# 08_-_CPU_USB.net
KiCad netlist of a schematic drawn in Altium Designer
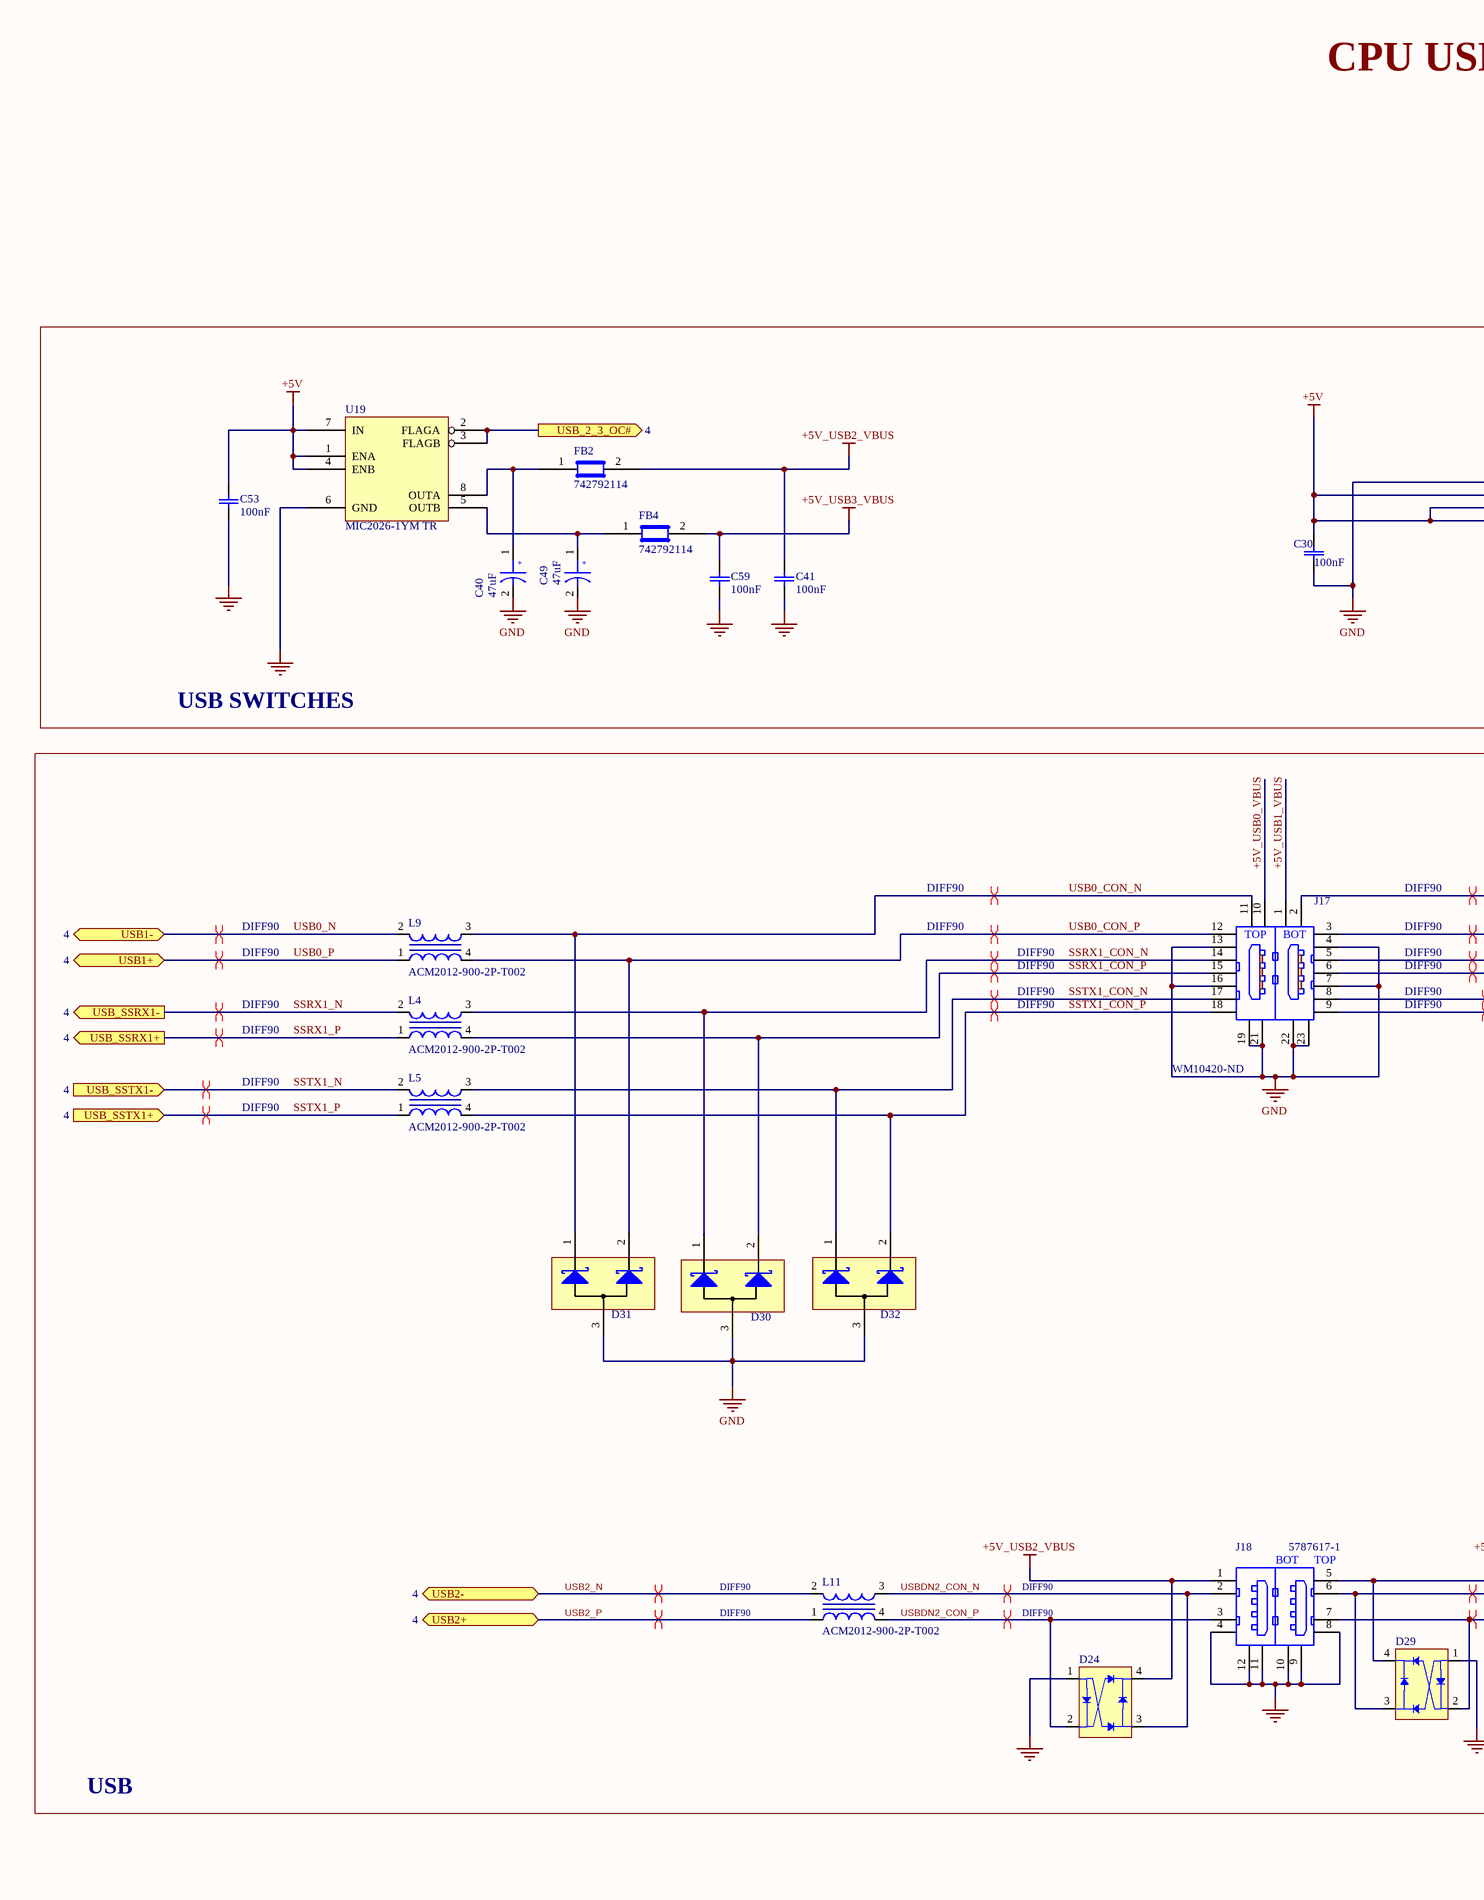
[diagram p0: [08] - CPU USB.SchDoc, left]
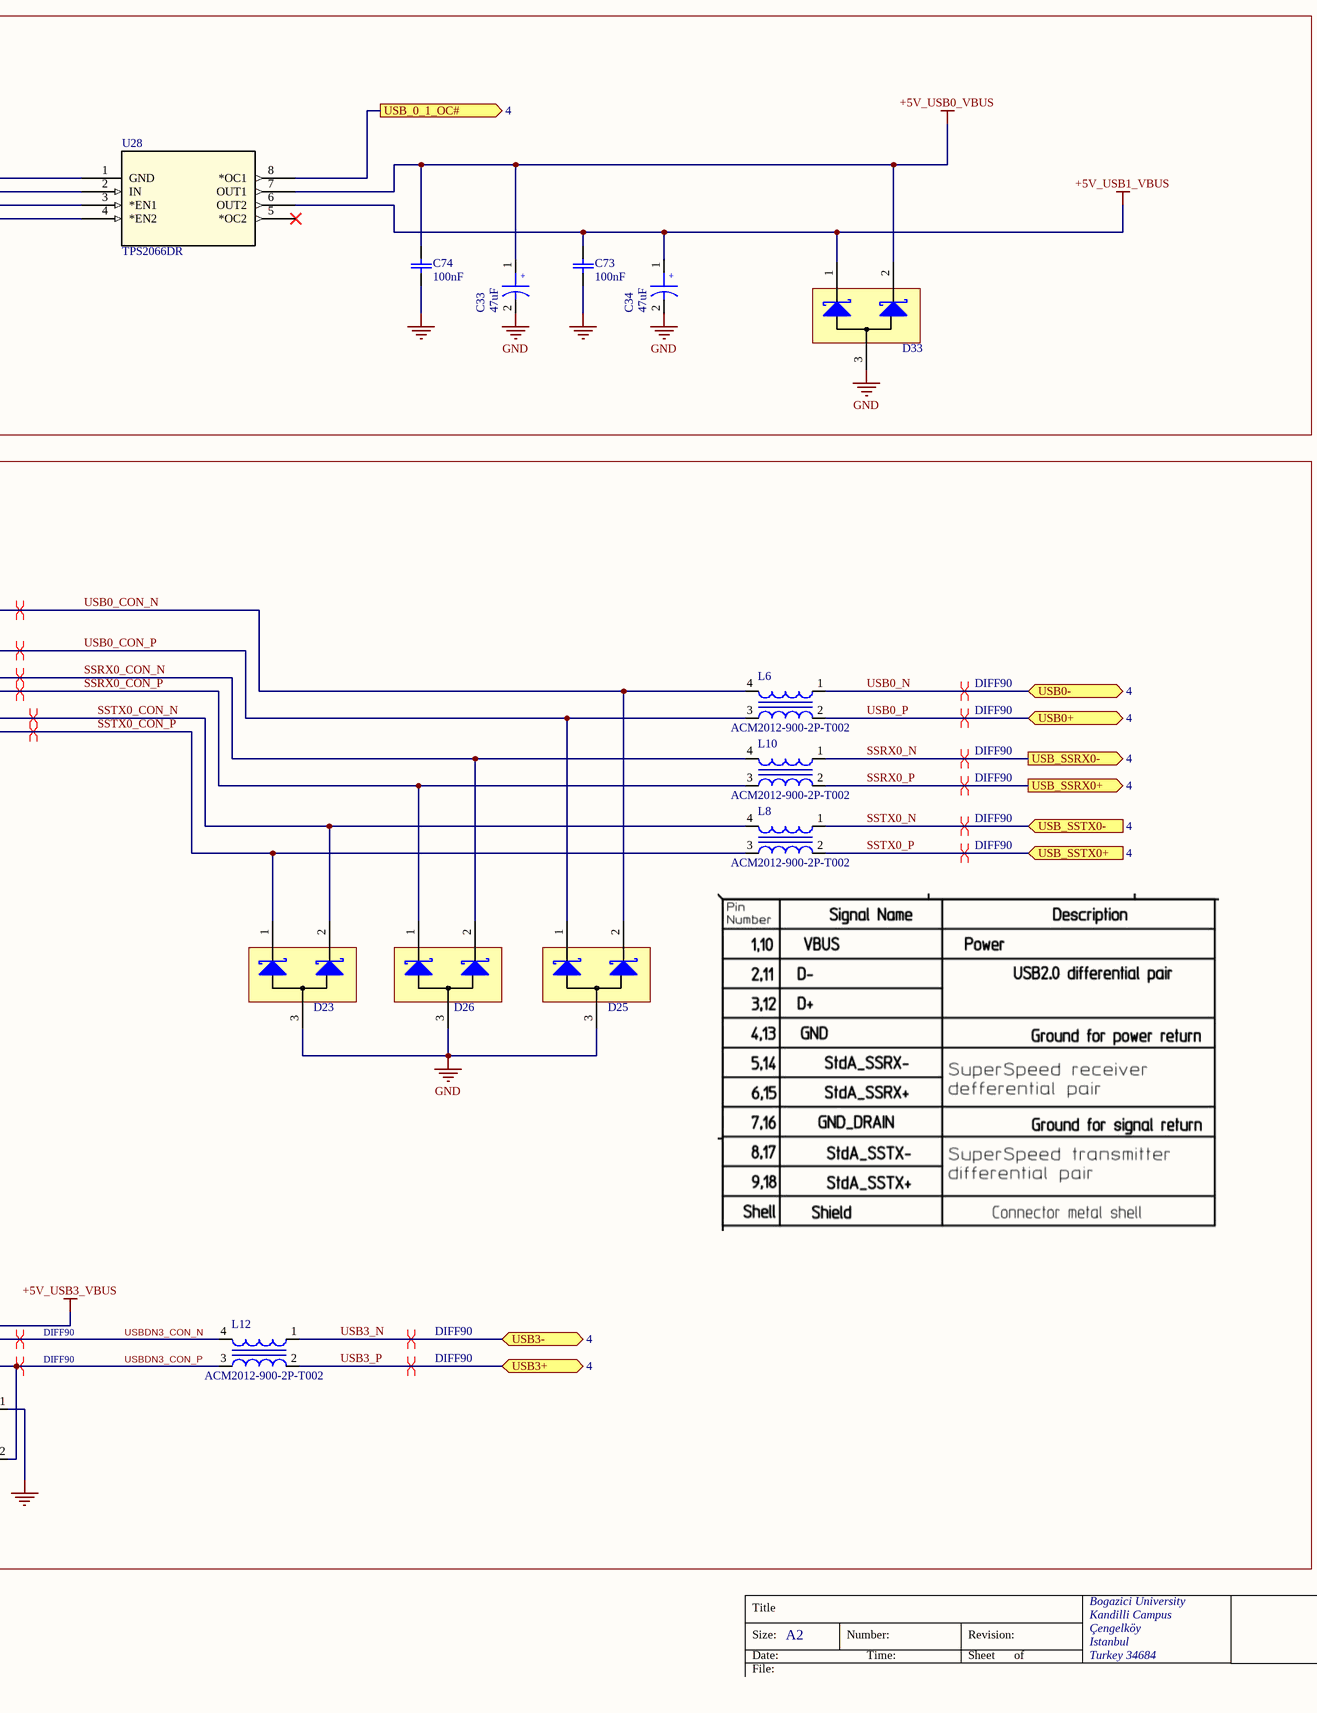
[diagram p1: [08] - CPU USB.SchDoc, right]

(export (version "E")
  (design (tool "Eeschema 10.0.6"))
  (components
    (comp (ref "C30")
      (value "100nF")
      (footprint "C0402")
      (description "CAP CER 0.1UF 50V X8R 0603")
      (fields (field (name "TOLERANCE") "±10%"))
      (libsource (lib "SYNCBOX_V3I1") (part "CL05A104KA5NNNC"))
    )
    (comp (ref "C33")
      (value "47uF")
      (footprint "CAP_P-B")
      (description "CAP ALUM POLY 47UF 20% 16V SMD")
      (fields
        (field (name "TOLERANCE") "±20%")
        (field (name ".CHECKED PCB") "CHK")
        (field (name ".CHECKED SCH") "CHK")
      )
      (libsource (lib "SYNCBOX_V3I1") (part "PCG1C470MCL1GS"))
    )
    (comp (ref "C34")
      (value "47uF")
      (footprint "CAP_P-B")
      (description "CAP ALUM POLY 47UF 20% 16V SMD")
      (fields
        (field (name "TOLERANCE") "±20%")
        (field (name ".CHECKED PCB") "CHK")
        (field (name ".CHECKED SCH") "CHK")
      )
      (libsource (lib "SYNCBOX_V3I1") (part "PCG1C470MCL1GS"))
    )
    (comp (ref "C40")
      (value "47uF")
      (footprint "CAP_P-B")
      (description "CAP ALUM POLY 47UF 20% 16V SMD")
      (fields
        (field (name "TOLERANCE") "±20%")
        (field (name ".CHECKED PCB") "CHK")
        (field (name ".CHECKED SCH") "CHK")
      )
      (libsource (lib "SYNCBOX_V3I1") (part "PCG1C470MCL1GS"))
    )
    (comp (ref "C41")
      (value "100nF")
      (footprint "C0402")
      (description "CAP CER 0.1UF 50V X8R 0603")
      (fields (field (name "TOLERANCE") "±10%"))
      (libsource (lib "SYNCBOX_V3I1") (part "CL05A104KA5NNNC"))
    )
    (comp (ref "C49")
      (value "47uF")
      (footprint "CAP_P-B")
      (description "CAP ALUM POLY 47UF 20% 16V SMD")
      (fields
        (field (name "TOLERANCE") "±20%")
        (field (name ".CHECKED PCB") "CHK")
        (field (name ".CHECKED SCH") "CHK")
      )
      (libsource (lib "SYNCBOX_V3I1") (part "PCG1C470MCL1GS"))
    )
    (comp (ref "C53")
      (value "100nF")
      (footprint "C0402")
      (description "CAP CER 0.1UF 50V X8R 0603")
      (fields (field (name "TOLERANCE") "±10%"))
      (libsource (lib "SYNCBOX_V3I1") (part "CL05A104KA5NNNC"))
    )
    (comp (ref "C59")
      (value "100nF")
      (footprint "C0402")
      (description "CAP CER 0.1UF 50V X8R 0603")
      (fields (field (name "TOLERANCE") "±10%"))
      (libsource (lib "SYNCBOX_V3I1") (part "CL05A104KA5NNNC"))
    )
    (comp (ref "C73")
      (value "100nF")
      (footprint "C0402")
      (description "CAP CER 0.1UF 50V X8R 0603")
      (fields (field (name "TOLERANCE") "±10%"))
      (libsource (lib "SYNCBOX_V3I1") (part "CL05A104KA5NNNC"))
    )
    (comp (ref "C74")
      (value "100nF")
      (footprint "C0402")
      (description "CAP CER 0.1UF 50V X8R 0603")
      (fields (field (name "TOLERANCE") "±10%"))
      (libsource (lib "SYNCBOX_V3I1") (part "CL05A104KA5NNNC"))
    )
    (comp (ref "D23")
      (value "ESD5V3U2U03FH6327XTSA1")
      (footprint "PG-TSLP-3-7")
      (description "TVS DIODE 5.3V 15V TSFP-3")
      (fields
        (field (name "BASE PART NUMBER") "ESD5V3")
        (field (name ".CHECKED PCB") "CHK")
        (field (name ".CHECKED SCH") "CHK")
      )
      (libsource (lib "SYNCBOX_V3I1") (part "ESD5V3U2U03FH6327XTSA1"))
    )
    (comp (ref "D24")
      (value "BAS4002ARPPE6327HTSA1")
      (footprint "SOT143B")
      (description "DIODE BRIDGE 40V 200MA SOT 143")
      (fields (field (name "BASE PART NUMBER") "BAS4002"))
      (libsource (lib "") (part "BAS4002ARPPE6327HTSA1_1"))
    )
    (comp (ref "D25")
      (value "ESD5V3U2U03FH6327XTSA1")
      (footprint "PG-TSLP-3-7")
      (description "TVS DIODE 5.3V 15V TSFP-3")
      (fields
        (field (name "BASE PART NUMBER") "ESD5V3")
        (field (name ".CHECKED PCB") "CHK")
        (field (name ".CHECKED SCH") "CHK")
      )
      (libsource (lib "SYNCBOX_V3I1") (part "ESD5V3U2U03FH6327XTSA1"))
    )
    (comp (ref "D26")
      (value "ESD5V3U2U03FH6327XTSA1")
      (footprint "PG-TSLP-3-7")
      (description "TVS DIODE 5.3V 15V TSFP-3")
      (fields
        (field (name "BASE PART NUMBER") "ESD5V3")
        (field (name ".CHECKED PCB") "CHK")
        (field (name ".CHECKED SCH") "CHK")
      )
      (libsource (lib "SYNCBOX_V3I1") (part "ESD5V3U2U03FH6327XTSA1"))
    )
    (comp (ref "D29")
      (value "BAS4002ARPPE6327HTSA1")
      (footprint "SOT143B")
      (description "DIODE BRIDGE 40V 200MA SOT 143")
      (fields (field (name "BASE PART NUMBER") "BAS4002"))
      (libsource (lib "SYNCBOX_V3I1") (part "BAS4002ARPPE6327HTSA1"))
    )
    (comp (ref "D30")
      (value "ESD5V3U2U03FH6327XTSA1")
      (footprint "PG-TSLP-3-7")
      (description "TVS DIODE 5.3V 15V TSFP-3")
      (fields
        (field (name "BASE PART NUMBER") "ESD5V3")
        (field (name ".CHECKED PCB") "CHK")
        (field (name ".CHECKED SCH") "CHK")
      )
      (libsource (lib "SYNCBOX_V3I1") (part "ESD5V3U2U03FH6327XTSA1"))
    )
    (comp (ref "D31")
      (value "ESD5V3U2U03FH6327XTSA1")
      (footprint "PG-TSLP-3-7")
      (description "TVS DIODE 5.3V 15V TSFP-3")
      (fields
        (field (name "BASE PART NUMBER") "ESD5V3")
        (field (name ".CHECKED PCB") "CHK")
        (field (name ".CHECKED SCH") "CHK")
      )
      (libsource (lib "SYNCBOX_V3I1") (part "ESD5V3U2U03FH6327XTSA1"))
    )
    (comp (ref "D32")
      (value "ESD5V3U2U03FH6327XTSA1")
      (footprint "PG-TSLP-3-7")
      (description "TVS DIODE 5.3V 15V TSFP-3")
      (fields
        (field (name "BASE PART NUMBER") "ESD5V3")
        (field (name ".CHECKED PCB") "CHK")
        (field (name ".CHECKED SCH") "CHK")
      )
      (libsource (lib "SYNCBOX_V3I1") (part "ESD5V3U2U03FH6327XTSA1"))
    )
    (comp (ref "D33")
      (value "ESD5V3U2U03FH6327XTSA1")
      (footprint "PG-TSLP-3-7")
      (description "TVS DIODE 5.3V 15V TSFP-3")
      (fields
        (field (name "BASE PART NUMBER") "ESD5V3")
        (field (name ".CHECKED PCB") "CHK")
        (field (name ".CHECKED SCH") "CHK")
      )
      (libsource (lib "SYNCBOX_V3I1") (part "ESD5V3U2U03FH6327XTSA1"))
    )
    (comp (ref "FB2")
      (value "742792114")
      (footprint "Ferrite bead")
      (description "FERRITE BEAD 50 OHM 1206 1LN")
      (fields (field (name ".CHECKED PCB") "CHK") (field (name ".CHECKED SCH") "CHK"))
      (libsource (lib "SYNCBOX_V3I1") (part "FB742792114"))
    )
    (comp (ref "FB4")
      (value "742792114")
      (footprint "Ferrite bead")
      (description "FERRITE BEAD 50 OHM 1206 1LN")
      (fields (field (name ".CHECKED PCB") "CHK") (field (name ".CHECKED SCH") "CHK"))
      (libsource (lib "SYNCBOX_V3I1") (part "FB742792114"))
    )
    (comp (ref "J17")
      (value "WM10420-ND")
      (footprint "USB 3 STACK")
      (description "USB 3.0 RA DUAL REC TH TYPE A")
      (fields (field (name ".CHECKED PCB") "CHK") (field (name ".CHECKED SCH") "CHK"))
      (libsource (lib "SYNCBOX_V3I1") (part "USB 3"))
    )
    (comp (ref "J18")
      (value "5787617-1")
      (footprint "USB-2A")
      (description "CONN RCPT R/A 4OVER4POS GOLD PCB")
      (fields
        (field (name "MANUFACTURER") "TE Connectivity")
        (field (name ".CHECKED PCB") "CHK")
        (field (name ".CHECKED SCH") "CHK")
      )
      (libsource (lib "SYNCBOX_V3I1") (part "5787617-1"))
    )
    (comp (ref "L4")
      (value "ACM2012-900-2P-T002")
      (footprint "iMX6 Rex Development Baseboard V1I1_PCB:ACM2012")
      (description "CHOKE COMM MODE 90 OHM .4A SMD")
      (fields
        (field (name "MANUFACTURER") "TDK Corporation")
        (field (name "TOLERANCE") "±1%")
        (field (name ".CHECKED PCB") "CHK")
        (field (name ".CHECKED SCH") "CHK")
      )
      (libsource (lib "SYNCBOX_V3I1") (part "ACM2012-900-2P-T002"))
    )
    (comp (ref "L5")
      (value "ACM2012-900-2P-T002")
      (footprint "iMX6 Rex Development Baseboard V1I1_PCB:ACM2012")
      (description "CHOKE COMM MODE 90 OHM .4A SMD")
      (fields
        (field (name "MANUFACTURER") "TDK Corporation")
        (field (name "TOLERANCE") "±1%")
        (field (name ".CHECKED PCB") "CHK")
        (field (name ".CHECKED SCH") "CHK")
      )
      (libsource (lib "SYNCBOX_V3I1") (part "ACM2012-900-2P-T002"))
    )
    (comp (ref "L6")
      (value "ACM2012-900-2P-T002")
      (footprint "iMX6 Rex Development Baseboard V1I1_PCB:ACM2012")
      (description "CHOKE COMM MODE 90 OHM .4A SMD")
      (fields
        (field (name "MANUFACTURER") "TDK Corporation")
        (field (name "TOLERANCE") "±1%")
        (field (name ".CHECKED PCB") "CHK")
        (field (name ".CHECKED SCH") "CHK")
      )
      (libsource (lib "SYNCBOX_V3I1") (part "ACM2012-900-2P-T002"))
    )
    (comp (ref "L8")
      (value "ACM2012-900-2P-T002")
      (footprint "iMX6 Rex Development Baseboard V1I1_PCB:ACM2012")
      (description "CHOKE COMM MODE 90 OHM .4A SMD")
      (fields
        (field (name "MANUFACTURER") "TDK Corporation")
        (field (name "TOLERANCE") "±1%")
        (field (name ".CHECKED PCB") "CHK")
        (field (name ".CHECKED SCH") "CHK")
      )
      (libsource (lib "SYNCBOX_V3I1") (part "ACM2012-900-2P-T002"))
    )
    (comp (ref "L9")
      (value "ACM2012-900-2P-T002")
      (footprint "iMX6 Rex Development Baseboard V1I1_PCB:ACM2012")
      (description "CHOKE COMM MODE 90 OHM .4A SMD")
      (fields
        (field (name "MANUFACTURER") "TDK Corporation")
        (field (name "TOLERANCE") "±1%")
        (field (name ".CHECKED PCB") "CHK")
        (field (name ".CHECKED SCH") "CHK")
      )
      (libsource (lib "SYNCBOX_V3I1") (part "ACM2012-900-2P-T002"))
    )
    (comp (ref "L10")
      (value "ACM2012-900-2P-T002")
      (footprint "iMX6 Rex Development Baseboard V1I1_PCB:ACM2012")
      (description "CHOKE COMM MODE 90 OHM .4A SMD")
      (fields
        (field (name "MANUFACTURER") "TDK Corporation")
        (field (name "TOLERANCE") "±1%")
        (field (name ".CHECKED PCB") "CHK")
        (field (name ".CHECKED SCH") "CHK")
      )
      (libsource (lib "SYNCBOX_V3I1") (part "ACM2012-900-2P-T002"))
    )
    (comp (ref "L11")
      (value "ACM2012-900-2P-T002")
      (footprint "iMX6 Rex Development Baseboard V1I1_PCB:ACM2012")
      (description "CHOKE COMM MODE 90 OHM .4A SMD")
      (fields
        (field (name "MANUFACTURER") "TDK Corporation")
        (field (name "TOLERANCE") "±1%")
        (field (name ".CHECKED PCB") "CHK")
        (field (name ".CHECKED SCH") "CHK")
      )
      (libsource (lib "SYNCBOX_V3I1") (part "ACM2012-900-2P-T002"))
    )
    (comp (ref "L12")
      (value "ACM2012-900-2P-T002")
      (footprint "iMX6 Rex Development Baseboard V1I1_PCB:ACM2012")
      (description "CHOKE COMM MODE 90 OHM .4A SMD")
      (fields
        (field (name "MANUFACTURER") "TDK Corporation")
        (field (name "TOLERANCE") "±1%")
        (field (name ".CHECKED PCB") "CHK")
        (field (name ".CHECKED SCH") "CHK")
      )
      (libsource (lib "SYNCBOX_V3I1") (part "ACM2012-900-2P-T002"))
    )
    (comp (ref "U19")
      (value "MIC2026-1YM TR")
      (footprint "8_SOIC_3.9MM")
      (description "IC SW DISTRIBUTION 2CHAN 8SOIC")
      (fields
        (field (name "MANUFACTURER") "Micrel Inc")
        (field (name ".CHECKED PCB") "CHK")
        (field (name ".CHECKED SCH") "CHK")
      )
      (libsource (lib "SYNCBOX_V3I1") (part "MIC2026-1YM TR"))
    )
    (comp (ref "U28")
      (value "TPS2066DR")
      (footprint "D8")
      (description "IC PWR DIST SW DUAL 8SOIC")
      (fields (field (name "MANUFACTURER") "Texas Instruments") (field (name "BASE PART NUMBER") "TPS2066"))
      (libsource (lib "SYNCBOX_V3I1") (part "TPS2066DR"))
    )
  )
  (nets
    (net (code "1") (name "+5V") (class "Default")
      (node (ref "C30") (pin "2") (pinfunction "2_2") (pintype "passive"))
      (node (ref "C53") (pin "2") (pinfunction "2_2") (pintype "passive"))
      (node (ref "U19") (pin "1") (pinfunction "ENA_1") (pintype "passive"))
      (node (ref "U19") (pin "4") (pinfunction "ENB_4") (pintype "passive"))
      (node (ref "U19") (pin "7") (pinfunction "IN_7") (pintype "power_in"))
      (node (ref "U28") (pin "2") (pinfunction "IN_2") (pintype "input"))
      (node (ref "U28") (pin "3") (pinfunction "*EN1_3") (pintype "input"))
      (node (ref "U28") (pin "4") (pinfunction "*EN2_4") (pintype "input"))
    )
    (net (code "2") (name "+5V_USB0_VBUS") (class "Default")
      (node (ref "C33") (pin "1") (pinfunction "1_1") (pintype "passive"))
      (node (ref "C74") (pin "2") (pinfunction "2_2") (pintype "passive"))
      (node (ref "D33") (pin "2") (pinfunction "2_2") (pintype "passive"))
      (node (ref "J17") (pin "10") (pinfunction "VBUS2_10") (pintype "power_in"))
      (node (ref "U28") (pin "7") (pinfunction "OUT1_7") (pintype "output"))
    )
    (net (code "3") (name "+5V_USB1_VBUS") (class "Default")
      (node (ref "C34") (pin "1") (pinfunction "1_1") (pintype "passive"))
      (node (ref "C73") (pin "2") (pinfunction "2_2") (pintype "passive"))
      (node (ref "D33") (pin "1") (pinfunction "1_1") (pintype "passive"))
      (node (ref "J17") (pin "1") (pinfunction "VBUS1_1") (pintype "power_in"))
      (node (ref "U28") (pin "6") (pinfunction "OUT2_6") (pintype "output"))
    )
    (net (code "4") (name "+5V_USB2_VBUS") (class "Default")
      (node (ref "C41") (pin "2") (pinfunction "2_2") (pintype "passive"))
      (node (ref "D24") (pin "4") (pinfunction "4_4") (pintype "passive"))
      (node (ref "FB2") (pin "2") (pinfunction "2_2") (pintype "passive"))
      (node (ref "J18") (pin "1") (pinfunction "VBUS_1") (pintype "passive"))
    )
    (net (code "5") (name "+5V_USB3_VBUS") (class "Default")
      (node (ref "C59") (pin "2") (pinfunction "2_2") (pintype "passive"))
      (node (ref "D29") (pin "4") (pinfunction "4_4") (pintype "passive"))
      (node (ref "FB4") (pin "2") (pinfunction "2_2") (pintype "passive"))
      (node (ref "J18") (pin "5") (pinfunction "VBUS2_5") (pintype "passive"))
    )
    (net (code "6") (name "/SSRX0_CON_N") (class "Default")
      (node (ref "D26") (pin "2") (pinfunction "2_2") (pintype "passive"))
      (node (ref "J17") (pin "5") (pinfunction "SSRX0-_5") (pintype "passive"))
      (node (ref "L10") (pin "4") (pinfunction "4_4") (pintype "passive"))
    )
    (net (code "7") (name "/SSRX0_CON_P") (class "Default")
      (node (ref "D26") (pin "1") (pinfunction "1_1") (pintype "passive"))
      (node (ref "J17") (pin "6") (pinfunction "SSRX0+_6") (pintype "passive"))
      (node (ref "L10") (pin "3") (pinfunction "3_3") (pintype "passive"))
    )
    (net (code "8") (name "/SSRX0_N") (class "Default")
      (node (ref "L10") (pin "1") (pinfunction "1_1") (pintype "passive"))
    )
    (net (code "9") (name "/SSRX0_P") (class "Default")
      (node (ref "L10") (pin "2") (pinfunction "2_2") (pintype "passive"))
    )
    (net (code "10") (name "/SSRX1_CON_N") (class "Default")
      (node (ref "D30") (pin "1") (pinfunction "1_1") (pintype "passive"))
      (node (ref "J17") (pin "14") (pinfunction "SSRX2-_14") (pintype "passive"))
      (node (ref "L4") (pin "3") (pinfunction "3_3") (pintype "passive"))
    )
    (net (code "11") (name "/SSRX1_CON_P") (class "Default")
      (node (ref "D30") (pin "2") (pinfunction "2_2") (pintype "passive"))
      (node (ref "J17") (pin "15") (pinfunction "SSRX2+_15") (pintype "passive"))
      (node (ref "L4") (pin "4") (pinfunction "4_4") (pintype "passive"))
    )
    (net (code "12") (name "/SSRX1_N") (class "Default")
      (node (ref "L4") (pin "2") (pinfunction "2_2") (pintype "passive"))
    )
    (net (code "13") (name "/SSRX1_P") (class "Default")
      (node (ref "L4") (pin "1") (pinfunction "1_1") (pintype "passive"))
    )
    (net (code "14") (name "/SSTX0_CON_N") (class "Default")
      (node (ref "D23") (pin "2") (pinfunction "2_2") (pintype "passive"))
      (node (ref "J17") (pin "8") (pinfunction "SSTX0-_8") (pintype "passive"))
      (node (ref "L8") (pin "4") (pinfunction "4_4") (pintype "passive"))
    )
    (net (code "15") (name "/SSTX0_CON_P") (class "Default")
      (node (ref "D23") (pin "1") (pinfunction "1_1") (pintype "passive"))
      (node (ref "J17") (pin "9") (pinfunction "SSTX0+_9") (pintype "passive"))
      (node (ref "L8") (pin "3") (pinfunction "3_3") (pintype "passive"))
    )
    (net (code "16") (name "/SSTX0_N") (class "Default")
      (node (ref "L8") (pin "1") (pinfunction "1_1") (pintype "passive"))
    )
    (net (code "17") (name "/SSTX0_P") (class "Default")
      (node (ref "L8") (pin "2") (pinfunction "2_2") (pintype "passive"))
    )
    (net (code "18") (name "/SSTX1_CON_N") (class "Default")
      (node (ref "D32") (pin "1") (pinfunction "1_1") (pintype "passive"))
      (node (ref "J17") (pin "17") (pinfunction "SSTX2-_17") (pintype "passive"))
      (node (ref "L5") (pin "3") (pinfunction "3_3") (pintype "passive"))
    )
    (net (code "19") (name "/SSTX1_CON_P") (class "Default")
      (node (ref "D32") (pin "2") (pinfunction "2_2") (pintype "passive"))
      (node (ref "J17") (pin "18") (pinfunction "SSTX2+_18") (pintype "passive"))
      (node (ref "L5") (pin "4") (pinfunction "4_4") (pintype "passive"))
    )
    (net (code "20") (name "/SSTX1_N") (class "Default")
      (node (ref "L5") (pin "2") (pinfunction "2_2") (pintype "passive"))
    )
    (net (code "21") (name "/SSTX1_P") (class "Default")
      (node (ref "L5") (pin "1") (pinfunction "1_1") (pintype "passive"))
    )
    (net (code "22") (name "/USB0_CON_N") (class "Default")
      (node (ref "D25") (pin "2") (pinfunction "2_2") (pintype "passive"))
      (node (ref "D31") (pin "1") (pinfunction "1_1") (pintype "passive"))
      (node (ref "J17") (pin "11") (pinfunction "D2-_11") (pintype "passive"))
      (node (ref "J17") (pin "2") (pinfunction "D1-_2") (pintype "passive"))
      (node (ref "L6") (pin "4") (pinfunction "4_4") (pintype "passive"))
      (node (ref "L9") (pin "3") (pinfunction "3_3") (pintype "passive"))
    )
    (net (code "23") (name "/USB0_CON_P") (class "Default")
      (node (ref "D25") (pin "1") (pinfunction "1_1") (pintype "passive"))
      (node (ref "D31") (pin "2") (pinfunction "2_2") (pintype "passive"))
      (node (ref "J17") (pin "12") (pinfunction "D2+_12") (pintype "passive"))
      (node (ref "J17") (pin "3") (pinfunction "D1+_3") (pintype "passive"))
      (node (ref "L6") (pin "3") (pinfunction "3_3") (pintype "passive"))
      (node (ref "L9") (pin "4") (pinfunction "4_4") (pintype "passive"))
    )
    (net (code "24") (name "/USB0_N") (class "Default")
      (node (ref "L6") (pin "1") (pinfunction "1_1") (pintype "passive"))
      (node (ref "L9") (pin "2") (pinfunction "2_2") (pintype "passive"))
    )
    (net (code "25") (name "/USB0_P") (class "Default")
      (node (ref "L6") (pin "2") (pinfunction "2_2") (pintype "passive"))
      (node (ref "L9") (pin "1") (pinfunction "1_1") (pintype "passive"))
    )
    (net (code "26") (name "/USB2_N") (class "Default")
      (node (ref "L11") (pin "2") (pinfunction "2_2") (pintype "passive"))
    )
    (net (code "27") (name "/USB2_P") (class "Default")
      (node (ref "L11") (pin "1") (pinfunction "1_1") (pintype "passive"))
    )
    (net (code "28") (name "/USB3_N") (class "Default")
      (node (ref "L12") (pin "1") (pinfunction "1_1") (pintype "passive"))
    )
    (net (code "29") (name "/USB3_P") (class "Default")
      (node (ref "L12") (pin "2") (pinfunction "2_2") (pintype "passive"))
    )
    (net (code "30") (name "/USBDN2_CON_N") (class "Default")
      (node (ref "D24") (pin "3") (pinfunction "3_3") (pintype "passive"))
      (node (ref "J18") (pin "2") (pinfunction "D-_2") (pintype "passive"))
      (node (ref "L11") (pin "3") (pinfunction "3_3") (pintype "passive"))
    )
    (net (code "31") (name "/USBDN2_CON_P") (class "Default")
      (node (ref "D24") (pin "2") (pinfunction "2_2") (pintype "passive"))
      (node (ref "J18") (pin "3") (pinfunction "D+_3") (pintype "passive"))
      (node (ref "L11") (pin "4") (pinfunction "4_4") (pintype "passive"))
    )
    (net (code "32") (name "/USBDN3_CON_N") (class "Default")
      (node (ref "D29") (pin "3") (pinfunction "3_3") (pintype "passive"))
      (node (ref "J18") (pin "6") (pinfunction "D2-_6") (pintype "passive"))
      (node (ref "L12") (pin "4") (pinfunction "4_4") (pintype "passive"))
    )
    (net (code "33") (name "/USBDN3_CON_P") (class "Default")
      (node (ref "D29") (pin "2") (pinfunction "2_2") (pintype "passive"))
      (node (ref "J18") (pin "7") (pinfunction "D2+_7") (pintype "passive"))
      (node (ref "L12") (pin "3") (pinfunction "3_3") (pintype "passive"))
    )
    (net (code "34") (name "/USB_0_1_OC#") (class "Default")
      (node (ref "U28") (pin "8") (pinfunction "*OC1_8") (pintype "output"))
    )
    (net (code "35") (name "/USB_2_3_OC#") (class "Default")
      (node (ref "U19") (pin "2") (pinfunction "FLAGA_2") (pintype "passive"))
      (node (ref "U19") (pin "3") (pinfunction "FLAGB_3") (pintype "passive"))
    )
    (net (code "36") (name "GND") (class "Default")
      (node (ref "C30") (pin "1") (pinfunction "1_1") (pintype "passive"))
      (node (ref "C33") (pin "2") (pinfunction "2_2") (pintype "passive"))
      (node (ref "C34") (pin "2") (pinfunction "2_2") (pintype "passive"))
      (node (ref "C40") (pin "2") (pinfunction "2_2") (pintype "passive"))
      (node (ref "C41") (pin "1") (pinfunction "1_1") (pintype "passive"))
      (node (ref "C49") (pin "2") (pinfunction "2_2") (pintype "passive"))
      (node (ref "C53") (pin "1") (pinfunction "1_1") (pintype "passive"))
      (node (ref "C59") (pin "1") (pinfunction "1_1") (pintype "passive"))
      (node (ref "C73") (pin "1") (pinfunction "1_1") (pintype "passive"))
      (node (ref "C74") (pin "1") (pinfunction "1_1") (pintype "passive"))
      (node (ref "D23") (pin "3") (pinfunction "3_3") (pintype "passive"))
      (node (ref "D24") (pin "1") (pinfunction "1_1") (pintype "passive"))
      (node (ref "D25") (pin "3") (pinfunction "3_3") (pintype "passive"))
      (node (ref "D26") (pin "3") (pinfunction "3_3") (pintype "passive"))
      (node (ref "D29") (pin "1") (pinfunction "1_1") (pintype "passive"))
      (node (ref "D30") (pin "3") (pinfunction "3_3") (pintype "passive"))
      (node (ref "D31") (pin "3") (pinfunction "3_3") (pintype "passive"))
      (node (ref "D32") (pin "3") (pinfunction "3_3") (pintype "passive"))
      (node (ref "D33") (pin "3") (pinfunction "3_3") (pintype "passive"))
      (node (ref "J17") (pin "13") (pinfunction "GND_13") (pintype "power_in"))
      (node (ref "J17") (pin "16") (pinfunction "GND_DRAIN2_16") (pintype "passive"))
      (node (ref "J17") (pin "19") (pinfunction "SHIELD_19") (pintype "passive"))
      (node (ref "J17") (pin "21") (pinfunction "SHIELD_21") (pintype "passive"))
      (node (ref "J17") (pin "22") (pinfunction "SHIELD_22") (pintype "passive"))
      (node (ref "J17") (pin "23") (pinfunction "SHIELD_23") (pintype "passive"))
      (node (ref "J17") (pin "4") (pinfunction "GND_4") (pintype "power_in"))
      (node (ref "J17") (pin "7") (pinfunction "GND_DRAIN1_7") (pintype "passive"))
      (node (ref "J18") (pin "10") (pinfunction "SHIELD_10") (pintype "passive"))
      (node (ref "J18") (pin "11") (pinfunction "SHIELD_11") (pintype "passive"))
      (node (ref "J18") (pin "12") (pinfunction "SHIELD_12") (pintype "passive"))
      (node (ref "J18") (pin "4") (pinfunction "GND_4") (pintype "passive"))
      (node (ref "J18") (pin "8") (pinfunction "GND_8") (pintype "passive"))
      (node (ref "J18") (pin "9") (pinfunction "SHIELD_9") (pintype "passive"))
      (node (ref "U19") (pin "6") (pinfunction "GND_6") (pintype "power_in"))
      (node (ref "U28") (pin "1") (pinfunction "GND_1") (pintype "power_in"))
    )
    (net (code "37") (name "Net-(U19-OUTA)") (class "Default")
      (node (ref "C40") (pin "1") (pinfunction "1_1") (pintype "passive"))
      (node (ref "FB2") (pin "1") (pinfunction "1_1") (pintype "passive"))
      (node (ref "U19") (pin "8") (pinfunction "OUTA_8") (pintype "passive"))
    )
    (net (code "38") (name "Net-(U19-OUTB)") (class "Default")
      (node (ref "C49") (pin "1") (pinfunction "1_1") (pintype "passive"))
      (node (ref "FB4") (pin "1") (pinfunction "1_1") (pintype "passive"))
      (node (ref "U19") (pin "5") (pinfunction "OUTB_5") (pintype "passive"))
    )
    (net (code "39") (name "unconnected-(U28-*OC2-Pad5)") (class "Default")
      (node (ref "U28") (pin "5") (pinfunction "*OC2_5") (pintype "output+no_connect"))
    )
  )
)
